# chibasai_board.net
KiCad netlist of a schematic drawn in EAGLE
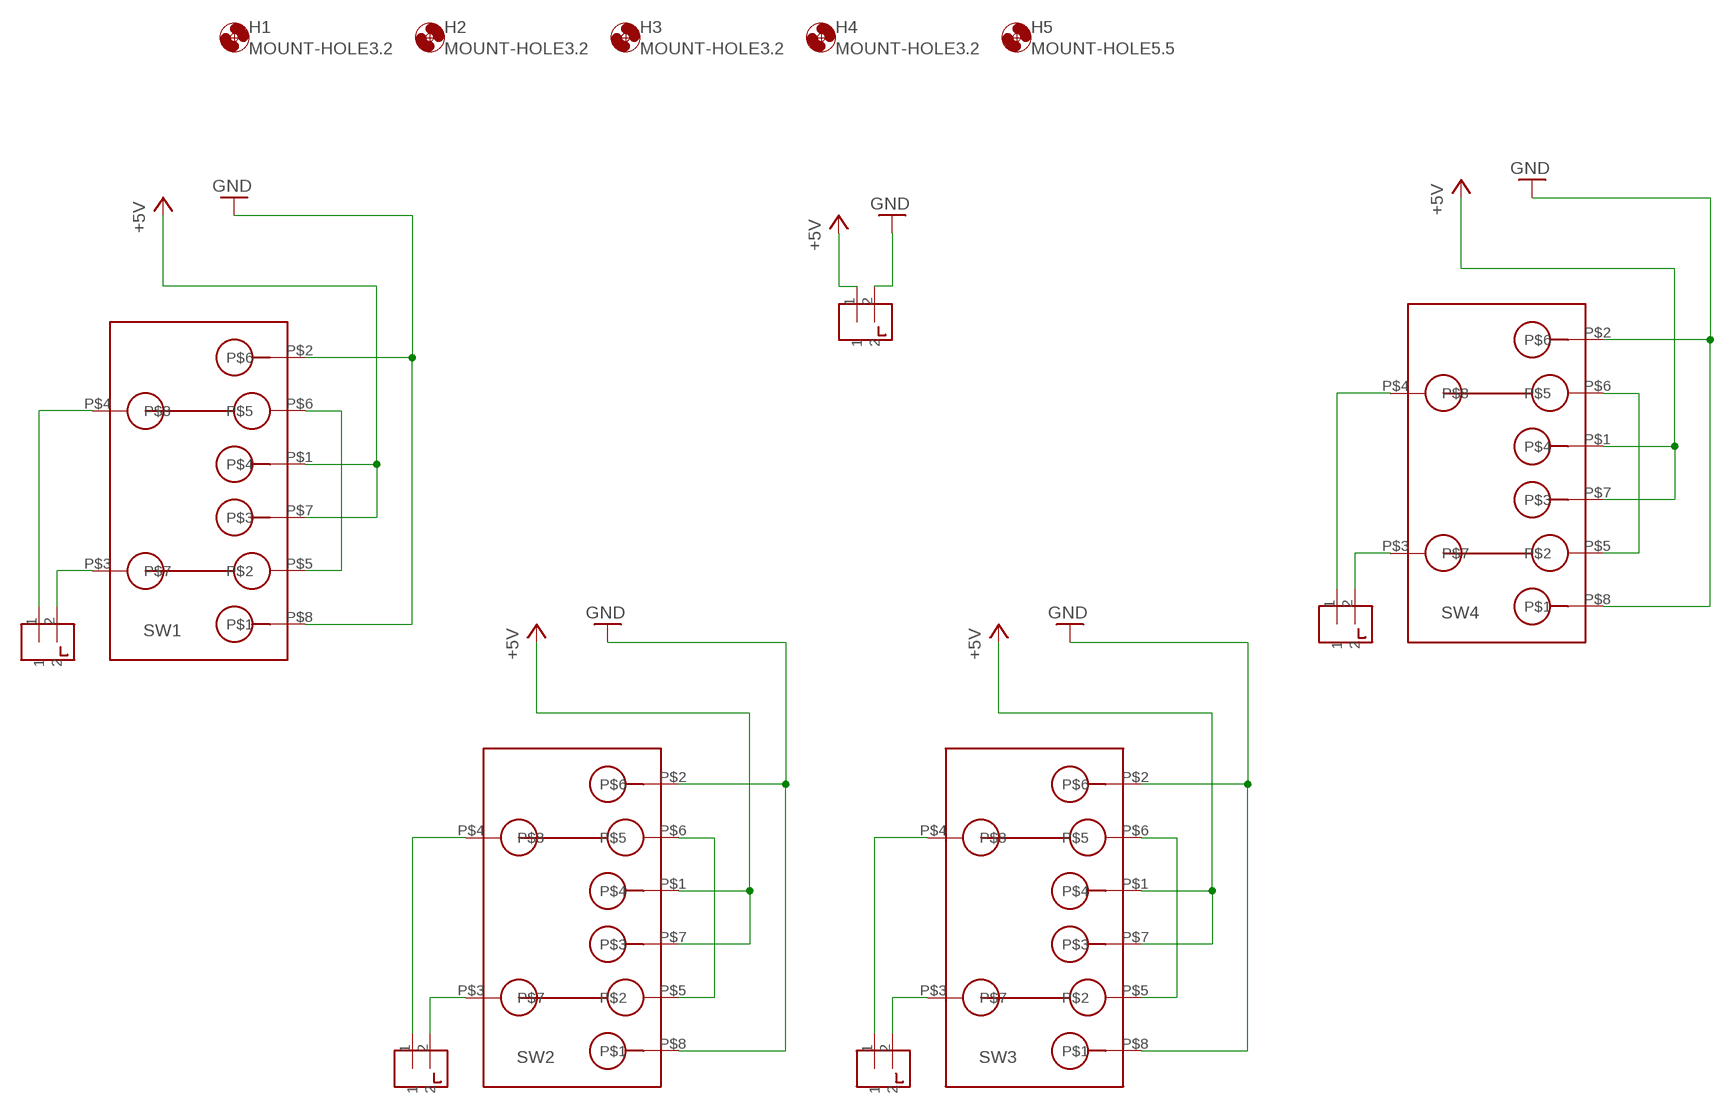
[diagram p0: schematic, sheet 1]

(export (version "E")
  (design (tool "Eeschema 10.0.6"))
  (components
    (comp (ref "CONNECTOR1")
      (value "2PIN")
      (footprint "eagle-import:2PIN")
      (libsource (lib "eagle-import") (part "2PIN"))
    )
    (comp (ref "CONNECTOR2")
      (value "2PIN")
      (footprint "eagle-import:2PIN")
      (libsource (lib "eagle-import") (part "2PIN"))
    )
    (comp (ref "CONNECTOR3")
      (value "2PIN")
      (footprint "eagle-import:2PIN")
      (libsource (lib "eagle-import") (part "2PIN"))
    )
    (comp (ref "CONNECTOR4")
      (value "2PIN")
      (footprint "eagle-import:2PIN")
      (libsource (lib "eagle-import") (part "2PIN"))
    )
    (comp (ref "CONNECTOR5")
      (value "2PIN")
      (footprint "eagle-import:2PIN")
      (libsource (lib "eagle-import") (part "2PIN"))
    )
    (comp (ref "H1")
      (value "MOUNT-HOLE3.2")
      (footprint "eagle-import:3,2")
      (libsource (lib "eagle-import") (part "MOUNT-HOLE3.2"))
    )
    (comp (ref "H2")
      (value "MOUNT-HOLE3.2")
      (footprint "eagle-import:3,2")
      (libsource (lib "eagle-import") (part "MOUNT-HOLE3.2"))
    )
    (comp (ref "H3")
      (value "MOUNT-HOLE3.2")
      (footprint "eagle-import:3,2")
      (libsource (lib "eagle-import") (part "MOUNT-HOLE3.2"))
    )
    (comp (ref "H4")
      (value "MOUNT-HOLE3.2")
      (footprint "eagle-import:3,2")
      (libsource (lib "eagle-import") (part "MOUNT-HOLE3.2"))
    )
    (comp (ref "H5")
      (value "MOUNT-HOLE5.5")
      (footprint "eagle-import:5,5")
      (libsource (lib "eagle-import") (part "MOUNT-HOLE5.5"))
    )
    (comp (ref "SW1")
      (value "ちばロボのSW")
      (footprint "eagle-import:SWのフートプリント")
      (libsource (lib "eagle-import") (part "ちばロボのSW"))
    )
    (comp (ref "SW2")
      (value "ちばロボのSW")
      (footprint "eagle-import:SWのフートプリント")
      (libsource (lib "eagle-import") (part "ちばロボのSW"))
    )
    (comp (ref "SW3")
      (value "ちばロボのSW")
      (footprint "eagle-import:SWのフートプリント")
      (libsource (lib "eagle-import") (part "ちばロボのSW"))
    )
    (comp (ref "SW4")
      (value "ちばロボのSW")
      (footprint "eagle-import:SWのフートプリント")
      (libsource (lib "eagle-import") (part "ちばロボのSW"))
    )
  )
  (nets
    (net (code "1") (name "+5V") (class "Default")
      (node (ref "CONNECTOR5") (pin "1") (pinfunction "1_1") (pintype "bidirectional"))
      (node (ref "SW1") (pin "P$1") (pinfunction "P$4_P$1") (pintype "bidirectional"))
      (node (ref "SW1") (pin "P$7") (pinfunction "P$3_P$7") (pintype "bidirectional"))
      (node (ref "SW2") (pin "P$1") (pinfunction "P$4_P$1") (pintype "bidirectional"))
      (node (ref "SW2") (pin "P$7") (pinfunction "P$3_P$7") (pintype "bidirectional"))
      (node (ref "SW3") (pin "P$1") (pinfunction "P$4_P$1") (pintype "bidirectional"))
      (node (ref "SW3") (pin "P$7") (pinfunction "P$3_P$7") (pintype "bidirectional"))
      (node (ref "SW4") (pin "P$1") (pinfunction "P$4_P$1") (pintype "bidirectional"))
      (node (ref "SW4") (pin "P$7") (pinfunction "P$3_P$7") (pintype "bidirectional"))
    )
    (net (code "2") (name "GND") (class "Default")
      (node (ref "CONNECTOR5") (pin "2") (pinfunction "2_2") (pintype "bidirectional"))
      (node (ref "SW1") (pin "P$2") (pinfunction "P$6_P$2") (pintype "bidirectional"))
      (node (ref "SW1") (pin "P$8") (pinfunction "P$1_P$8") (pintype "bidirectional"))
      (node (ref "SW2") (pin "P$2") (pinfunction "P$6_P$2") (pintype "bidirectional"))
      (node (ref "SW2") (pin "P$8") (pinfunction "P$1_P$8") (pintype "bidirectional"))
      (node (ref "SW3") (pin "P$2") (pinfunction "P$6_P$2") (pintype "bidirectional"))
      (node (ref "SW3") (pin "P$8") (pinfunction "P$1_P$8") (pintype "bidirectional"))
      (node (ref "SW4") (pin "P$2") (pinfunction "P$6_P$2") (pintype "bidirectional"))
      (node (ref "SW4") (pin "P$8") (pinfunction "P$1_P$8") (pintype "bidirectional"))
    )
    (net (code "3") (name "Net-(SW1-P$2)") (class "Default")
      (node (ref "SW1") (pin "P$5") (pinfunction "P$2_P$5") (pintype "bidirectional"))
      (node (ref "SW1") (pin "P$6") (pinfunction "P$5_P$6") (pintype "bidirectional"))
    )
    (net (code "4") (name "Net-(SW1-P$7)") (class "Default")
      (node (ref "CONNECTOR1") (pin "2") (pinfunction "2_2") (pintype "bidirectional"))
      (node (ref "SW1") (pin "P$3") (pinfunction "P$7_P$3") (pintype "bidirectional"))
    )
    (net (code "5") (name "Net-(SW1-P$8)") (class "Default")
      (node (ref "CONNECTOR1") (pin "1") (pinfunction "1_1") (pintype "bidirectional"))
      (node (ref "SW1") (pin "P$4") (pinfunction "P$8_P$4") (pintype "bidirectional"))
    )
    (net (code "6") (name "Net-(SW2-P$2)") (class "Default")
      (node (ref "SW2") (pin "P$5") (pinfunction "P$2_P$5") (pintype "bidirectional"))
      (node (ref "SW2") (pin "P$6") (pinfunction "P$5_P$6") (pintype "bidirectional"))
    )
    (net (code "7") (name "Net-(SW2-P$7)") (class "Default")
      (node (ref "CONNECTOR2") (pin "2") (pinfunction "2_2") (pintype "bidirectional"))
      (node (ref "SW2") (pin "P$3") (pinfunction "P$7_P$3") (pintype "bidirectional"))
    )
    (net (code "8") (name "Net-(SW2-P$8)") (class "Default")
      (node (ref "CONNECTOR2") (pin "1") (pinfunction "1_1") (pintype "bidirectional"))
      (node (ref "SW2") (pin "P$4") (pinfunction "P$8_P$4") (pintype "bidirectional"))
    )
    (net (code "9") (name "Net-(SW3-P$2)") (class "Default")
      (node (ref "SW3") (pin "P$5") (pinfunction "P$2_P$5") (pintype "bidirectional"))
      (node (ref "SW3") (pin "P$6") (pinfunction "P$5_P$6") (pintype "bidirectional"))
    )
    (net (code "10") (name "Net-(SW3-P$7)") (class "Default")
      (node (ref "CONNECTOR3") (pin "2") (pinfunction "2_2") (pintype "bidirectional"))
      (node (ref "SW3") (pin "P$3") (pinfunction "P$7_P$3") (pintype "bidirectional"))
    )
    (net (code "11") (name "Net-(SW3-P$8)") (class "Default")
      (node (ref "CONNECTOR3") (pin "1") (pinfunction "1_1") (pintype "bidirectional"))
      (node (ref "SW3") (pin "P$4") (pinfunction "P$8_P$4") (pintype "bidirectional"))
    )
    (net (code "12") (name "Net-(SW4-P$2)") (class "Default")
      (node (ref "SW4") (pin "P$5") (pinfunction "P$2_P$5") (pintype "bidirectional"))
      (node (ref "SW4") (pin "P$6") (pinfunction "P$5_P$6") (pintype "bidirectional"))
    )
    (net (code "13") (name "Net-(SW4-P$7)") (class "Default")
      (node (ref "CONNECTOR4") (pin "2") (pinfunction "2_2") (pintype "bidirectional"))
      (node (ref "SW4") (pin "P$3") (pinfunction "P$7_P$3") (pintype "bidirectional"))
    )
    (net (code "14") (name "Net-(SW4-P$8)") (class "Default")
      (node (ref "CONNECTOR4") (pin "1") (pinfunction "1_1") (pintype "bidirectional"))
      (node (ref "SW4") (pin "P$4") (pinfunction "P$8_P$4") (pintype "bidirectional"))
    )
  )
)
